# P-MOS_NPN.net
KiCad netlist of a schematic drawn in Altium Designer
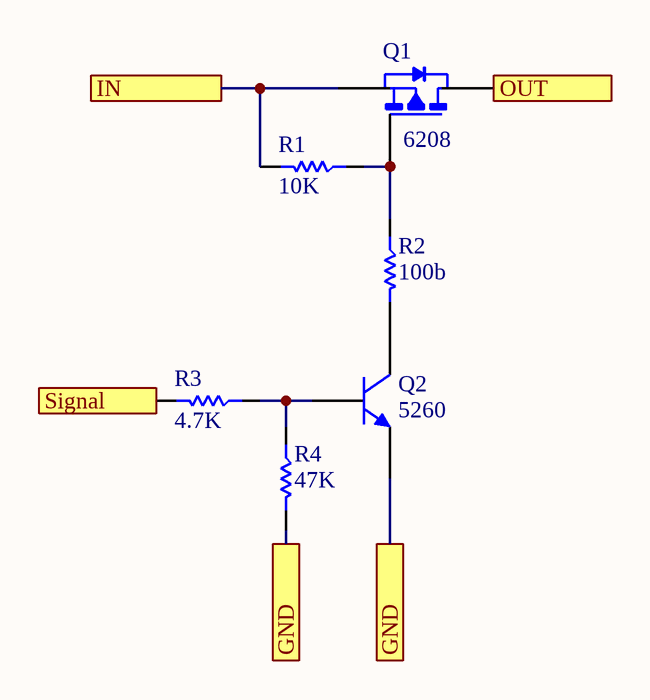
[diagram p0: P-MOS_NPN.SchDoc]

(export (version "E")
  (design (tool "Eeschema 10.0.6"))
  (components
    (comp (ref "Q1")
      (value "P-Channel")
      (footprint "SOT23_N")
      (description "P-Channel MOSFET")
      (fields (field (name "INFLOW") "6208"))
      (libsource (lib "aKaReZa") (part "Semi_MOSFET_Si2301DS"))
    )
    (comp (ref "Q2")
      (value "NPN")
      (footprint "SOT23_N")
      (description "NPN Switching Transistors")
      (fields (field (name "INFLOW") "5260"))
      (libsource (lib "aKaReZa") (part "Semi_BJT_2N2222_SMD"))
    )
    (comp (ref "R1")
      (value "10K")
      (footprint "RES 0805 (2012X06L)")
      (description "Resistor")
      (libsource (lib "aKaReZa") (part "Res_SMD_0805"))
    )
    (comp (ref "R2")
      (value "100b")
      (footprint "RES 0805 (2012X06L)")
      (description "Resistor")
      (libsource (lib "aKaReZa") (part "Res_SMD_0805"))
    )
    (comp (ref "R3")
      (value "4.7K")
      (footprint "RES 0805 (2012X06L)")
      (description "Resistor")
      (libsource (lib "aKaReZa") (part "Res_SMD_0805"))
    )
    (comp (ref "R4")
      (value "47K")
      (footprint "RES 0805 (2012X06L)")
      (description "Resistor")
      (libsource (lib "aKaReZa") (part "Res_SMD_0805"))
    )
  )
  (nets
    (net (code "1") (name "/GND") (class "Default")
      (node (ref "Q2") (pin "2") (pinfunction "E_2") (pintype "passive"))
      (node (ref "R4") (pin "2") (pinfunction "2_2") (pintype "passive"))
    )
    (net (code "2") (name "/IN") (class "Default")
      (node (ref "Q1") (pin "2") (pinfunction "S_2") (pintype "passive"))
      (node (ref "R1") (pin "2") (pinfunction "2_2") (pintype "passive"))
    )
    (net (code "3") (name "/OUT") (class "Default")
      (node (ref "Q1") (pin "3") (pinfunction "D_3") (pintype "passive"))
    )
    (net (code "4") (name "/Signal") (class "Default")
      (node (ref "R3") (pin "2") (pinfunction "2_2") (pintype "passive"))
    )
    (net (code "5") (name "Net-(Q1-G)") (class "Default")
      (node (ref "Q1") (pin "1") (pinfunction "G_1") (pintype "passive"))
      (node (ref "R1") (pin "1") (pinfunction "1_1") (pintype "passive"))
      (node (ref "R2") (pin "1") (pinfunction "1_1") (pintype "passive"))
    )
    (net (code "6") (name "Net-(Q2-B)") (class "Default")
      (node (ref "Q2") (pin "1") (pinfunction "B_1") (pintype "passive"))
      (node (ref "R3") (pin "1") (pinfunction "1_1") (pintype "passive"))
      (node (ref "R4") (pin "1") (pinfunction "1_1") (pintype "passive"))
    )
    (net (code "7") (name "Net-(Q2-C)") (class "Default")
      (node (ref "Q2") (pin "3") (pinfunction "C_3") (pintype "passive"))
      (node (ref "R2") (pin "2") (pinfunction "2_2") (pintype "passive"))
    )
  )
)
